# emg.net
KiCad netlist of a schematic drawn in EAGLE
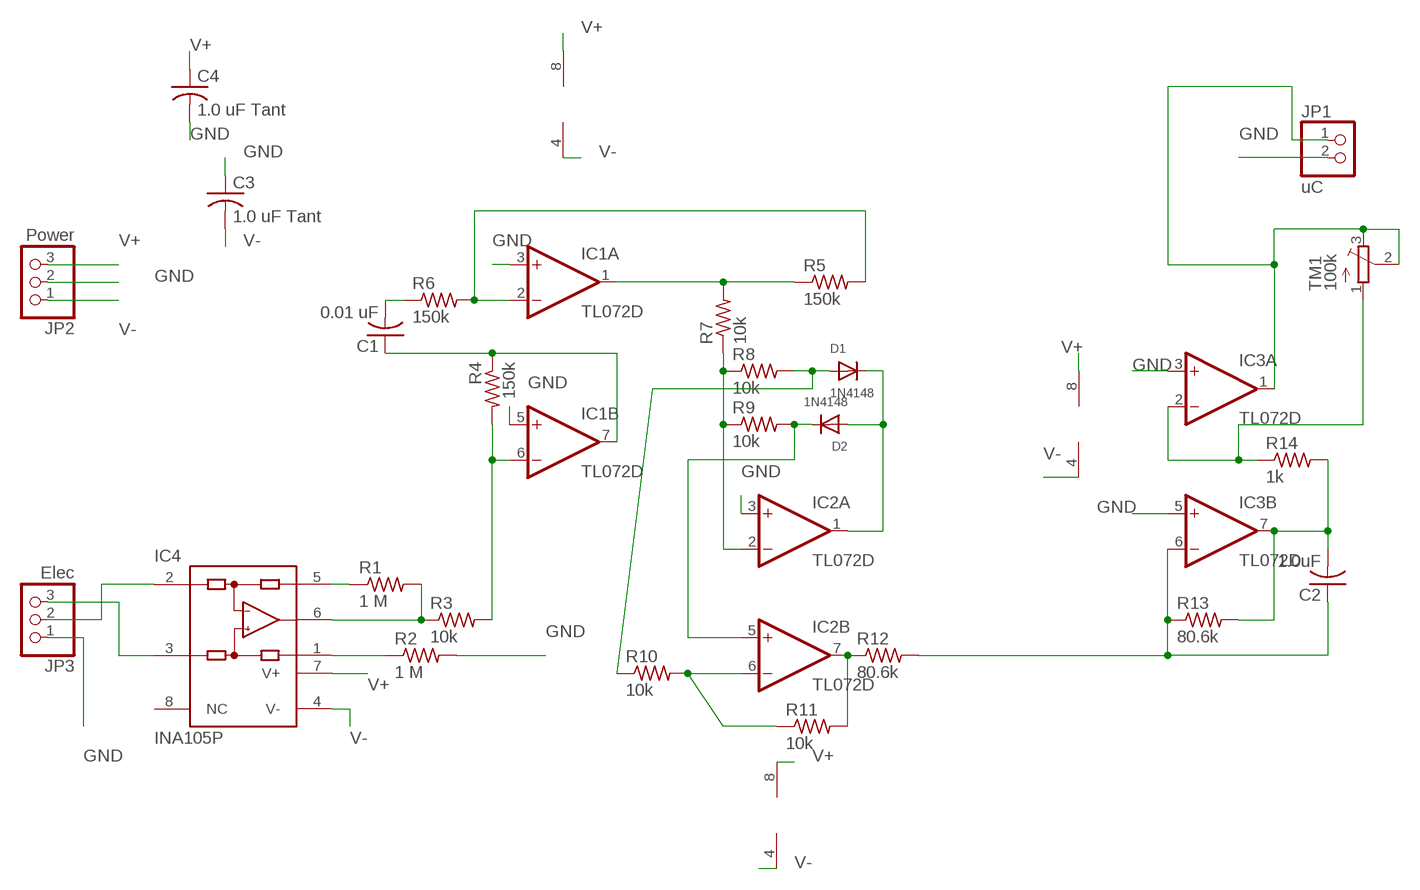
[diagram p0: schematic, sheet 1]

(export (version "E")
  (design (tool "Eeschema 10.0.6"))
  (components
    (comp (ref "C1")
      (value "0.01 uF")
      (footprint "eagle-import:C0603")
      (libsource (lib "eagle-import") (part "C-USC0603"))
    )
    (comp (ref "C2")
      (value "1.0uF")
      (footprint "eagle-import:C0603")
      (libsource (lib "eagle-import") (part "C-USC0603"))
    )
    (comp (ref "C3")
      (value "1.0 uF Tant")
      (footprint "eagle-import:C0805")
      (libsource (lib "eagle-import") (part "C-USC0805"))
    )
    (comp (ref "C4")
      (value "1.0 uF Tant")
      (footprint "eagle-import:C0805")
      (libsource (lib "eagle-import") (part "C-USC0805"))
    )
    (comp (ref "D1")
      (value "1N4148")
      (footprint "eagle-import:DO-1N4148")
      (libsource (lib "eagle-import") (part "DIODEDO-1N4148"))
    )
    (comp (ref "D2")
      (value "1N4148")
      (footprint "eagle-import:DO-1N4148")
      (libsource (lib "eagle-import") (part "DIODEDO-1N4148"))
    )
    (comp (ref "IC1")
      (value "TL072D")
      (footprint "eagle-import:SO08")
      (libsource (lib "eagle-import") (part "TL072D"))
    )
    (comp (ref "IC2")
      (value "TL072D")
      (footprint "eagle-import:SO08")
      (libsource (lib "eagle-import") (part "TL072D"))
    )
    (comp (ref "IC3")
      (value "TL072D")
      (footprint "eagle-import:SO08")
      (libsource (lib "eagle-import") (part "TL072D"))
    )
    (comp (ref "IC4")
      (value "INA105P")
      (footprint "eagle-import:DIL08")
      (fields (field (name "MF") "TEXAS INSTRUMENTS") (field (name "MPN") "INA105KP"))
      (libsource (lib "eagle-import") (part "INA105P"))
    )
    (comp (ref "JP1")
      (value "uC")
      (footprint "eagle-import:1X02")
      (libsource (lib "eagle-import") (part "PINHD-1X2"))
    )
    (comp (ref "JP2")
      (value "Power")
      (footprint "eagle-import:1X03")
      (libsource (lib "eagle-import") (part "PINHD-1X3"))
    )
    (comp (ref "JP3")
      (value "Elec")
      (footprint "eagle-import:1X03")
      (libsource (lib "eagle-import") (part "PINHD-1X3"))
    )
    (comp (ref "R1")
      (value "1 M")
      (footprint "eagle-import:R0603")
      (libsource (lib "eagle-import") (part "R-US_R0603"))
    )
    (comp (ref "R2")
      (value "1 M")
      (footprint "eagle-import:R0603")
      (libsource (lib "eagle-import") (part "R-US_R0603"))
    )
    (comp (ref "R3")
      (value "10k")
      (footprint "eagle-import:R0603")
      (libsource (lib "eagle-import") (part "R-US_R0603"))
    )
    (comp (ref "R4")
      (value "150k")
      (footprint "eagle-import:R0603")
      (libsource (lib "eagle-import") (part "R-US_R0603"))
    )
    (comp (ref "R5")
      (value "150k")
      (footprint "eagle-import:R0603")
      (libsource (lib "eagle-import") (part "R-US_R0603"))
    )
    (comp (ref "R6")
      (value "150k")
      (footprint "eagle-import:R0603")
      (libsource (lib "eagle-import") (part "R-US_R0603"))
    )
    (comp (ref "R7")
      (value "10k")
      (footprint "eagle-import:R0603")
      (libsource (lib "eagle-import") (part "R-US_R0603"))
    )
    (comp (ref "R8")
      (value "10k")
      (footprint "eagle-import:R0603")
      (libsource (lib "eagle-import") (part "R-US_R0603"))
    )
    (comp (ref "R9")
      (value "10k")
      (footprint "eagle-import:R0603")
      (libsource (lib "eagle-import") (part "R-US_R0603"))
    )
    (comp (ref "R10")
      (value "10k")
      (footprint "eagle-import:R0603")
      (libsource (lib "eagle-import") (part "R-US_R0603"))
    )
    (comp (ref "R11")
      (value "10k")
      (footprint "eagle-import:R0603")
      (libsource (lib "eagle-import") (part "R-US_R0603"))
    )
    (comp (ref "R12")
      (value "80.6k")
      (footprint "eagle-import:R1206")
      (libsource (lib "eagle-import") (part "R-US_R1206"))
    )
    (comp (ref "R13")
      (value "80.6k")
      (footprint "eagle-import:R1206")
      (libsource (lib "eagle-import") (part "R-US_R1206"))
    )
    (comp (ref "R14")
      (value "1k")
      (footprint "eagle-import:R0603")
      (libsource (lib "eagle-import") (part "R-US_R0603"))
    )
    (comp (ref "TM1")
      (value "100k")
      (footprint "eagle-import:TC33X")
      (libsource (lib "eagle-import") (part "TRIMPOTTC33X"))
    )
  )
  (nets
    (net (code "1") (name "/GND") (class "Default")
      (node (ref "C3") (pin "1") (pinfunction "1_1") (pintype "passive"))
      (node (ref "C4") (pin "2") (pinfunction "2_2") (pintype "passive"))
      (node (ref "IC1") (pin "3") (pinfunction "+IN_3") (pintype "input"))
      (node (ref "IC1") (pin "5") (pinfunction "+IN_5") (pintype "input"))
      (node (ref "IC2") (pin "3") (pinfunction "+IN_3") (pintype "input"))
      (node (ref "IC3") (pin "3") (pinfunction "+IN_3") (pintype "input"))
      (node (ref "IC3") (pin "5") (pinfunction "+IN_5") (pintype "input"))
      (node (ref "JP1") (pin "2") (pinfunction "2_2") (pintype "passive"))
      (node (ref "JP2") (pin "2") (pinfunction "2_2") (pintype "passive"))
      (node (ref "JP3") (pin "1") (pinfunction "1_1") (pintype "passive"))
      (node (ref "R2") (pin "2") (pinfunction "2_2") (pintype "passive"))
    )
    (net (code "2") (name "/V+") (class "Default")
      (node (ref "C4") (pin "1") (pinfunction "1_1") (pintype "passive"))
      (node (ref "IC1") (pin "8") (pinfunction "V+_8") (pintype "power_in"))
      (node (ref "IC2") (pin "8") (pinfunction "V+_8") (pintype "power_in"))
      (node (ref "IC3") (pin "8") (pinfunction "V+_8") (pintype "power_in"))
      (node (ref "IC4") (pin "7") (pinfunction "V+_7") (pintype "power_in"))
      (node (ref "JP2") (pin "3") (pinfunction "3_3") (pintype "passive"))
    )
    (net (code "3") (name "/V-") (class "Default")
      (node (ref "C3") (pin "2") (pinfunction "2_2") (pintype "passive"))
      (node (ref "IC1") (pin "4") (pinfunction "V-_4") (pintype "power_in"))
      (node (ref "IC2") (pin "4") (pinfunction "V-_4") (pintype "power_in"))
      (node (ref "IC3") (pin "4") (pinfunction "V-_4") (pintype "power_in"))
      (node (ref "IC4") (pin "4") (pinfunction "V-_4") (pintype "power_in"))
      (node (ref "JP2") (pin "1") (pinfunction "1_1") (pintype "passive"))
    )
    (net (code "4") (name "Net-(C1-Pad2)") (class "Default")
      (node (ref "C1") (pin "2") (pinfunction "2_2") (pintype "passive"))
      (node (ref "R6") (pin "1") (pinfunction "1_1") (pintype "passive"))
    )
    (net (code "5") (name "Net-(D1-PadA)") (class "Default")
      (node (ref "D1") (pin "A") (pinfunction "A_A") (pintype "passive"))
      (node (ref "R10") (pin "1") (pinfunction "1_1") (pintype "passive"))
      (node (ref "R8") (pin "2") (pinfunction "2_2") (pintype "passive"))
    )
    (net (code "6") (name "Net-(IC1A--IN)") (class "Default")
      (node (ref "IC1") (pin "2") (pinfunction "-IN_2") (pintype "input"))
      (node (ref "R5") (pin "2") (pinfunction "2_2") (pintype "passive"))
      (node (ref "R6") (pin "2") (pinfunction "2_2") (pintype "passive"))
    )
    (net (code "7") (name "Net-(IC1A-OUT)") (class "Default")
      (node (ref "IC1") (pin "1") (pinfunction "OUT_1") (pintype "output"))
      (node (ref "R5") (pin "1") (pinfunction "1_1") (pintype "passive"))
      (node (ref "R7") (pin "2") (pinfunction "2_2") (pintype "passive"))
    )
    (net (code "8") (name "Net-(IC1B--IN)") (class "Default")
      (node (ref "IC1") (pin "6") (pinfunction "-IN_6") (pintype "input"))
      (node (ref "R3") (pin "2") (pinfunction "2_2") (pintype "passive"))
      (node (ref "R4") (pin "2") (pinfunction "2_2") (pintype "passive"))
    )
    (net (code "9") (name "Net-(IC1B-OUT)") (class "Default")
      (node (ref "C1") (pin "1") (pinfunction "1_1") (pintype "passive"))
      (node (ref "IC1") (pin "7") (pinfunction "OUT_7") (pintype "output"))
      (node (ref "R4") (pin "1") (pinfunction "1_1") (pintype "passive"))
    )
    (net (code "10") (name "Net-(IC2A--IN)") (class "Default")
      (node (ref "IC2") (pin "2") (pinfunction "-IN_2") (pintype "input"))
      (node (ref "R7") (pin "1") (pinfunction "1_1") (pintype "passive"))
      (node (ref "R8") (pin "1") (pinfunction "1_1") (pintype "passive"))
      (node (ref "R9") (pin "1") (pinfunction "1_1") (pintype "passive"))
    )
    (net (code "11") (name "Net-(IC2A-OUT)") (class "Default")
      (node (ref "D1") (pin "C") (pinfunction "C_C") (pintype "passive"))
      (node (ref "D2") (pin "A") (pinfunction "A_A") (pintype "passive"))
      (node (ref "IC2") (pin "1") (pinfunction "OUT_1") (pintype "output"))
    )
    (net (code "12") (name "Net-(IC2B-+IN)") (class "Default")
      (node (ref "D2") (pin "C") (pinfunction "C_C") (pintype "passive"))
      (node (ref "IC2") (pin "5") (pinfunction "+IN_5") (pintype "input"))
      (node (ref "R9") (pin "2") (pinfunction "2_2") (pintype "passive"))
    )
    (net (code "13") (name "Net-(IC2B--IN)") (class "Default")
      (node (ref "IC2") (pin "6") (pinfunction "-IN_6") (pintype "input"))
      (node (ref "R10") (pin "2") (pinfunction "2_2") (pintype "passive"))
      (node (ref "R11") (pin "1") (pinfunction "1_1") (pintype "passive"))
    )
    (net (code "14") (name "Net-(IC2B-OUT)") (class "Default")
      (node (ref "IC2") (pin "7") (pinfunction "OUT_7") (pintype "output"))
      (node (ref "R11") (pin "2") (pinfunction "2_2") (pintype "passive"))
      (node (ref "R12") (pin "1") (pinfunction "1_1") (pintype "passive"))
    )
    (net (code "15") (name "Net-(IC3A--IN)") (class "Default")
      (node (ref "IC3") (pin "2") (pinfunction "-IN_2") (pintype "input"))
      (node (ref "R14") (pin "1") (pinfunction "1_1") (pintype "passive"))
      (node (ref "TM1") (pin "1") (pinfunction "A_1") (pintype "passive"))
    )
    (net (code "16") (name "Net-(IC3A-OUT)") (class "Default")
      (node (ref "IC3") (pin "1") (pinfunction "OUT_1") (pintype "output"))
      (node (ref "JP1") (pin "1") (pinfunction "1_1") (pintype "passive"))
      (node (ref "TM1") (pin "2") (pinfunction "S_2") (pintype "passive"))
      (node (ref "TM1") (pin "3") (pinfunction "E_3") (pintype "passive"))
    )
    (net (code "17") (name "Net-(IC3B--IN)") (class "Default")
      (node (ref "C2") (pin "1") (pinfunction "1_1") (pintype "passive"))
      (node (ref "IC3") (pin "6") (pinfunction "-IN_6") (pintype "input"))
      (node (ref "R12") (pin "2") (pinfunction "2_2") (pintype "passive"))
      (node (ref "R13") (pin "1") (pinfunction "1_1") (pintype "passive"))
    )
    (net (code "18") (name "Net-(IC3B-OUT)") (class "Default")
      (node (ref "C2") (pin "2") (pinfunction "2_2") (pintype "passive"))
      (node (ref "IC3") (pin "7") (pinfunction "OUT_7") (pintype "output"))
      (node (ref "R13") (pin "2") (pinfunction "2_2") (pintype "passive"))
      (node (ref "R14") (pin "2") (pinfunction "2_2") (pintype "passive"))
    )
    (net (code "19") (name "Net-(IC4-+IN)") (class "Default")
      (node (ref "IC4") (pin "3") (pinfunction "+IN_3") (pintype "input"))
      (node (ref "JP3") (pin "3") (pinfunction "3_3") (pintype "passive"))
    )
    (net (code "20") (name "Net-(IC4--IN)") (class "Default")
      (node (ref "IC4") (pin "2") (pinfunction "-IN_2") (pintype "input"))
      (node (ref "JP3") (pin "2") (pinfunction "2_2") (pintype "passive"))
    )
    (net (code "21") (name "Net-(IC4-OUT)") (class "Default")
      (node (ref "IC4") (pin "6") (pinfunction "OUT_6") (pintype "output"))
      (node (ref "R1") (pin "2") (pinfunction "2_2") (pintype "passive"))
      (node (ref "R3") (pin "1") (pinfunction "1_1") (pintype "passive"))
    )
    (net (code "22") (name "Net-(IC4-REF)") (class "Default")
      (node (ref "IC4") (pin "1") (pinfunction "REF_1") (pintype "passive"))
      (node (ref "R2") (pin "1") (pinfunction "1_1") (pintype "passive"))
    )
    (net (code "23") (name "Net-(IC4-SENSE)") (class "Default")
      (node (ref "IC4") (pin "5") (pinfunction "SENSE_5") (pintype "passive"))
      (node (ref "R1") (pin "1") (pinfunction "1_1") (pintype "passive"))
    )
    (net (code "24") (name "unconnected-(IC4-NC-Pad8)") (class "Default")
      (node (ref "IC4") (pin "8") (pinfunction "NC_8") (pintype "no_connect"))
    )
  )
)
